# R107S1A.net
KiCad netlist of a schematic drawn in EAGLE
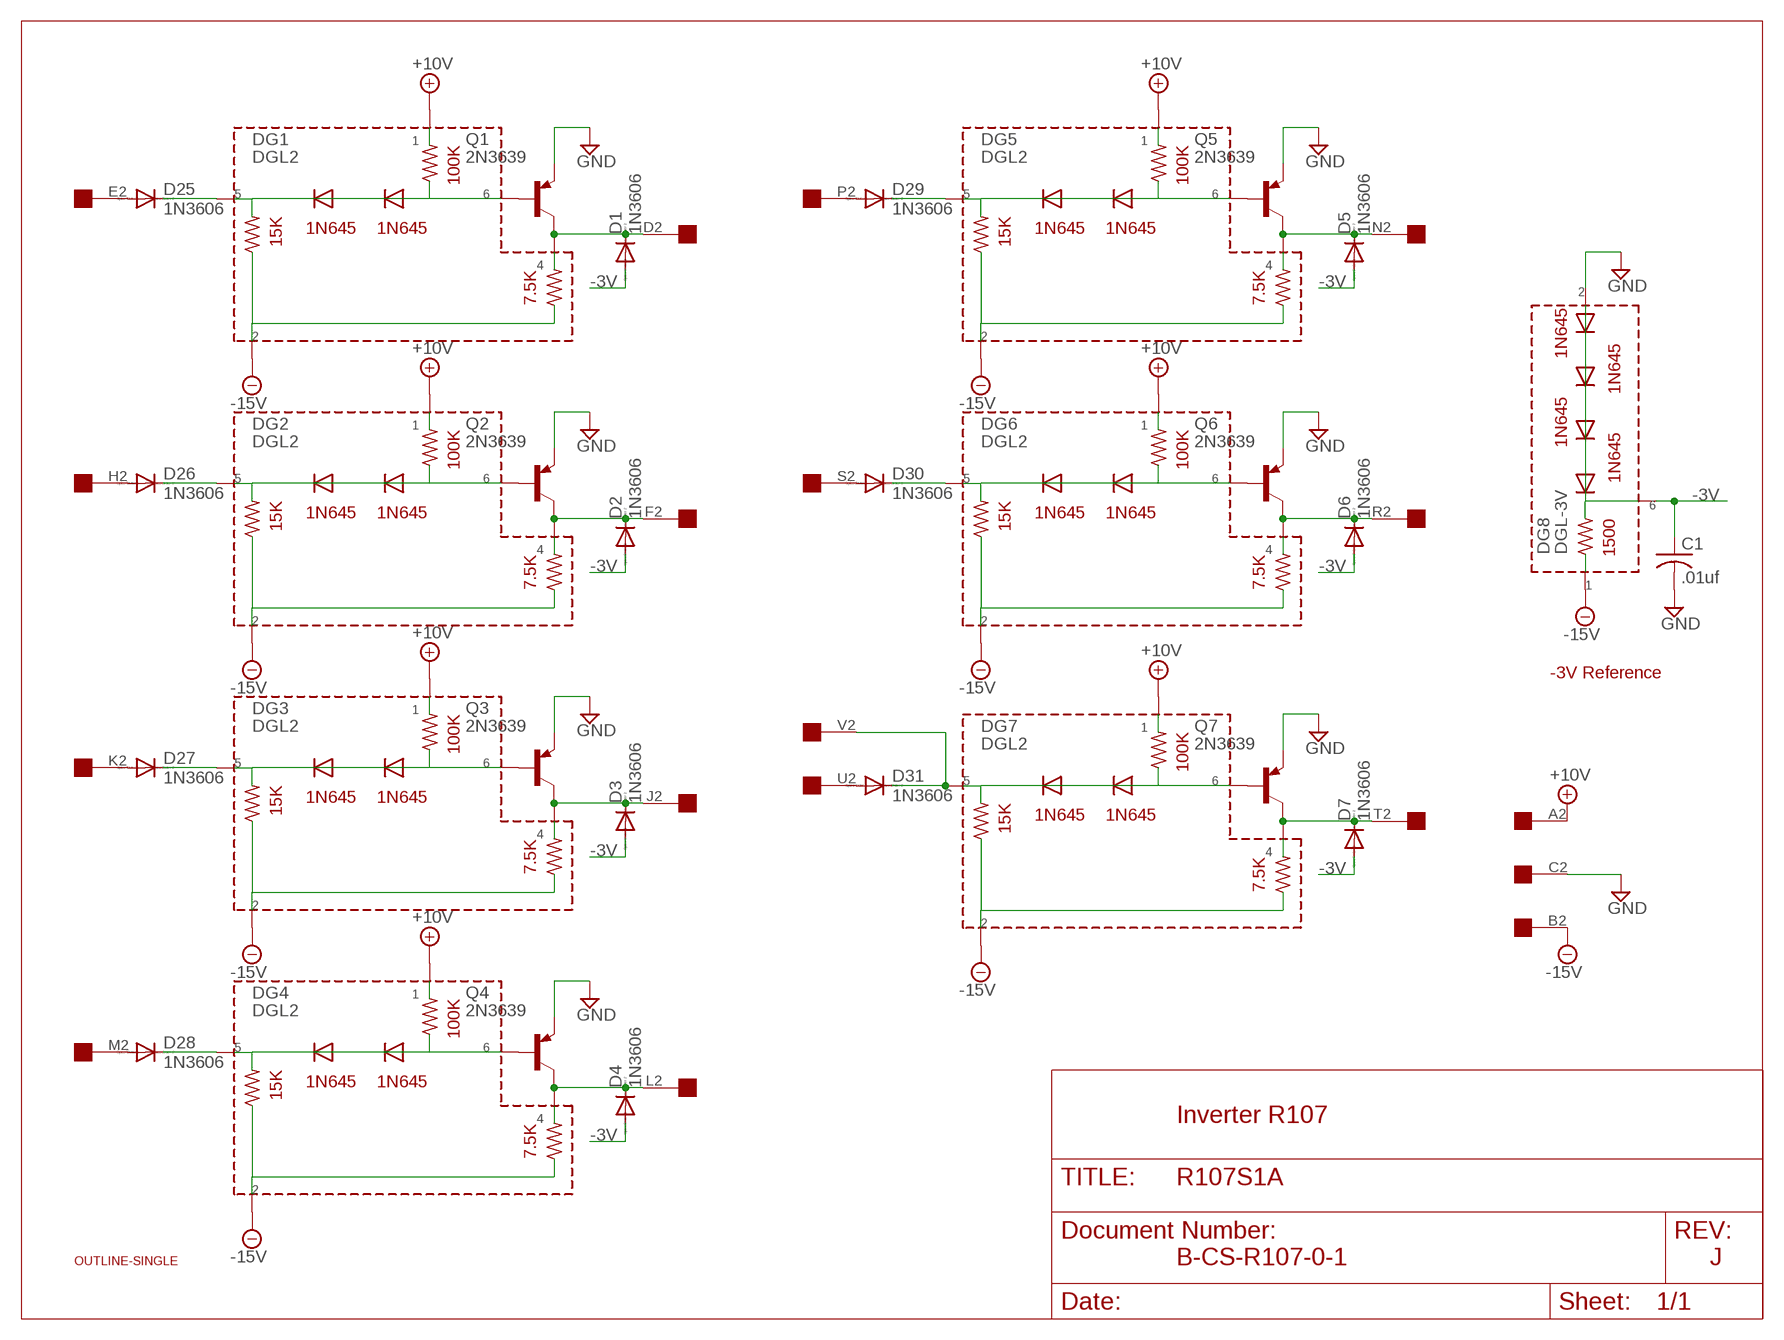
[diagram p0: schematic, sheet 1]

(export (version "E")
  (design (tool "Eeschema 10.0.6"))
  (components
    (comp (ref "C1")
      (value ".01uf")
      (footprint "eagle-import:C050-025X075")
      (libsource (lib "eagle-import") (part "C-US050-025X075"))
    )
    (comp (ref "D1")
      (value "1N3606")
      (footprint "eagle-import:DO35-10")
      (libsource (lib "eagle-import") (part "1N4148DO35-10"))
    )
    (comp (ref "D2")
      (value "1N3606")
      (footprint "eagle-import:DO35-10")
      (libsource (lib "eagle-import") (part "1N4148DO35-10"))
    )
    (comp (ref "D3")
      (value "1N3606")
      (footprint "eagle-import:DO35-10")
      (libsource (lib "eagle-import") (part "1N4148DO35-10"))
    )
    (comp (ref "D4")
      (value "1N3606")
      (footprint "eagle-import:DO35-10")
      (libsource (lib "eagle-import") (part "1N4148DO35-10"))
    )
    (comp (ref "D5")
      (value "1N3606")
      (footprint "eagle-import:DO35-10")
      (libsource (lib "eagle-import") (part "1N4148DO35-10"))
    )
    (comp (ref "D6")
      (value "1N3606")
      (footprint "eagle-import:DO35-10")
      (libsource (lib "eagle-import") (part "1N4148DO35-10"))
    )
    (comp (ref "D7")
      (value "1N3606")
      (footprint "eagle-import:DO35-10")
      (libsource (lib "eagle-import") (part "1N4148DO35-10"))
    )
    (comp (ref "D25")
      (value "1N3606")
      (footprint "eagle-import:DO35-10")
      (libsource (lib "eagle-import") (part "1N4148DO35-10"))
    )
    (comp (ref "D26")
      (value "1N3606")
      (footprint "eagle-import:DO35-10")
      (libsource (lib "eagle-import") (part "1N4148DO35-10"))
    )
    (comp (ref "D27")
      (value "1N3606")
      (footprint "eagle-import:DO35-10")
      (libsource (lib "eagle-import") (part "1N4148DO35-10"))
    )
    (comp (ref "D28")
      (value "1N3606")
      (footprint "eagle-import:DO35-10")
      (libsource (lib "eagle-import") (part "1N4148DO35-10"))
    )
    (comp (ref "D29")
      (value "1N3606")
      (footprint "eagle-import:DO35-10")
      (libsource (lib "eagle-import") (part "1N4148DO35-10"))
    )
    (comp (ref "D30")
      (value "1N3606")
      (footprint "eagle-import:DO35-10")
      (libsource (lib "eagle-import") (part "1N4148DO35-10"))
    )
    (comp (ref "D31")
      (value "1N3606")
      (footprint "eagle-import:DO35-10")
      (libsource (lib "eagle-import") (part "1N4148DO35-10"))
    )
    (comp (ref "DG1")
      (value "DGL2")
      (footprint "eagle-import:DGL2")
      (libsource (lib "eagle-import") (part "DGL2"))
    )
    (comp (ref "DG2")
      (value "DGL2")
      (footprint "eagle-import:DGL2")
      (libsource (lib "eagle-import") (part "DGL2"))
    )
    (comp (ref "DG3")
      (value "DGL2")
      (footprint "eagle-import:DGL2")
      (libsource (lib "eagle-import") (part "DGL2"))
    )
    (comp (ref "DG4")
      (value "DGL2")
      (footprint "eagle-import:DGL2")
      (libsource (lib "eagle-import") (part "DGL2"))
    )
    (comp (ref "DG5")
      (value "DGL2")
      (footprint "eagle-import:DGL2")
      (libsource (lib "eagle-import") (part "DGL2"))
    )
    (comp (ref "DG6")
      (value "DGL2")
      (footprint "eagle-import:DGL2")
      (libsource (lib "eagle-import") (part "DGL2"))
    )
    (comp (ref "DG7")
      (value "DGL2")
      (footprint "eagle-import:DGL2")
      (libsource (lib "eagle-import") (part "DGL2"))
    )
    (comp (ref "DG8")
      (value "DGL-3V")
      (footprint "eagle-import:DGL2")
      (libsource (lib "eagle-import") (part "DGL-3V"))
    )
    (comp (ref "Q1")
      (value "2N3639")
      (footprint "eagle-import:TO39")
      (libsource (lib "eagle-import") (part "2N3637"))
    )
    (comp (ref "Q2")
      (value "2N3639")
      (footprint "eagle-import:TO39")
      (libsource (lib "eagle-import") (part "2N3637"))
    )
    (comp (ref "Q3")
      (value "2N3639")
      (footprint "eagle-import:TO39")
      (libsource (lib "eagle-import") (part "2N3637"))
    )
    (comp (ref "Q4")
      (value "2N3639")
      (footprint "eagle-import:TO39")
      (libsource (lib "eagle-import") (part "2N3637"))
    )
    (comp (ref "Q5")
      (value "2N3639")
      (footprint "eagle-import:TO39")
      (libsource (lib "eagle-import") (part "2N3637"))
    )
    (comp (ref "Q6")
      (value "2N3639")
      (footprint "eagle-import:TO39")
      (libsource (lib "eagle-import") (part "2N3637"))
    )
    (comp (ref "Q7")
      (value "2N3639")
      (footprint "eagle-import:TO39")
      (libsource (lib "eagle-import") (part "2N3637"))
    )
    (comp (ref "U$1")
      (value "OUTLINE-SINGLE")
      (footprint "eagle-import:SINGLE")
      (libsource (lib "eagle-import") (part "OUTLINE-SINGLE"))
    )
    (comp (ref "U$2")
      (value "EDGE-1")
      (footprint "eagle-import:EDGE-CON1")
      (libsource (lib "eagle-import") (part "EDGE-1"))
    )
  )
  (nets
    (net (code "1") (name "+10V") (class "Default")
      (node (ref "DG1") (pin "P$1") (pinfunction "1_P$1") (pintype "passive"))
      (node (ref "DG2") (pin "P$1") (pinfunction "1_P$1") (pintype "passive"))
      (node (ref "DG3") (pin "P$1") (pinfunction "1_P$1") (pintype "passive"))
      (node (ref "DG4") (pin "P$1") (pinfunction "1_P$1") (pintype "passive"))
      (node (ref "DG5") (pin "P$1") (pinfunction "1_P$1") (pintype "passive"))
      (node (ref "DG6") (pin "P$1") (pinfunction "1_P$1") (pintype "passive"))
      (node (ref "DG7") (pin "P$1") (pinfunction "1_P$1") (pintype "passive"))
      (node (ref "U$2") (pin "A2") (pinfunction "1_A2") (pintype "bidirectional"))
    )
    (net (code "2") (name "-15V") (class "Default")
      (node (ref "DG1") (pin "P$2") (pinfunction "2_P$2") (pintype "passive"))
      (node (ref "DG2") (pin "P$2") (pinfunction "2_P$2") (pintype "passive"))
      (node (ref "DG3") (pin "P$2") (pinfunction "2_P$2") (pintype "passive"))
      (node (ref "DG4") (pin "P$2") (pinfunction "2_P$2") (pintype "passive"))
      (node (ref "DG5") (pin "P$2") (pinfunction "2_P$2") (pintype "passive"))
      (node (ref "DG6") (pin "P$2") (pinfunction "2_P$2") (pintype "passive"))
      (node (ref "DG7") (pin "P$2") (pinfunction "2_P$2") (pintype "passive"))
      (node (ref "DG8") (pin "P$1") (pinfunction "1_P$1") (pintype "passive"))
      (node (ref "U$2") (pin "B2") (pinfunction "1_B2") (pintype "bidirectional"))
    )
    (net (code "3") (name "/-3V") (class "Default")
      (node (ref "C1") (pin "1") (pinfunction "1_1") (pintype "passive"))
      (node (ref "D1") (pin "A") (pinfunction "A_A") (pintype "passive"))
      (node (ref "D2") (pin "A") (pinfunction "A_A") (pintype "passive"))
      (node (ref "D3") (pin "A") (pinfunction "A_A") (pintype "passive"))
      (node (ref "D4") (pin "A") (pinfunction "A_A") (pintype "passive"))
      (node (ref "D5") (pin "A") (pinfunction "A_A") (pintype "passive"))
      (node (ref "D6") (pin "A") (pinfunction "A_A") (pintype "passive"))
      (node (ref "D7") (pin "A") (pinfunction "A_A") (pintype "passive"))
      (node (ref "DG8") (pin "P$6") (pinfunction "6_P$6") (pintype "passive"))
    )
    (net (code "4") (name "GND") (class "Default")
      (node (ref "C1") (pin "2") (pinfunction "2_2") (pintype "passive"))
      (node (ref "DG8") (pin "P$2") (pinfunction "2_P$2") (pintype "passive"))
      (node (ref "Q1") (pin "1") (pinfunction "E_1") (pintype "passive"))
      (node (ref "Q2") (pin "1") (pinfunction "E_1") (pintype "passive"))
      (node (ref "Q3") (pin "1") (pinfunction "E_1") (pintype "passive"))
      (node (ref "Q4") (pin "1") (pinfunction "E_1") (pintype "passive"))
      (node (ref "Q5") (pin "1") (pinfunction "E_1") (pintype "passive"))
      (node (ref "Q6") (pin "1") (pinfunction "E_1") (pintype "passive"))
      (node (ref "Q7") (pin "1") (pinfunction "E_1") (pintype "passive"))
      (node (ref "U$2") (pin "C2") (pinfunction "1_C2") (pintype "bidirectional"))
    )
    (net (code "5") (name "Net-(DG1-4)") (class "Default")
      (node (ref "D1") (pin "C") (pinfunction "C_C") (pintype "passive"))
      (node (ref "DG1") (pin "P$4") (pinfunction "4_P$4") (pintype "passive"))
      (node (ref "Q1") (pin "3") (pinfunction "C_3") (pintype "passive"))
      (node (ref "U$2") (pin "D2") (pinfunction "1_D2") (pintype "bidirectional"))
    )
    (net (code "6") (name "Net-(DG1-5)") (class "Default")
      (node (ref "D25") (pin "C") (pinfunction "C_C") (pintype "passive"))
      (node (ref "DG1") (pin "P$5") (pinfunction "5_P$5") (pintype "passive"))
    )
    (net (code "7") (name "Net-(DG1-6)") (class "Default")
      (node (ref "DG1") (pin "P$6") (pinfunction "6_P$6") (pintype "passive"))
      (node (ref "Q1") (pin "2") (pinfunction "B_2") (pintype "passive"))
    )
    (net (code "8") (name "Net-(DG2-4)") (class "Default")
      (node (ref "D2") (pin "C") (pinfunction "C_C") (pintype "passive"))
      (node (ref "DG2") (pin "P$4") (pinfunction "4_P$4") (pintype "passive"))
      (node (ref "Q2") (pin "3") (pinfunction "C_3") (pintype "passive"))
      (node (ref "U$2") (pin "F2") (pinfunction "1_F2") (pintype "bidirectional"))
    )
    (net (code "9") (name "Net-(DG2-5)") (class "Default")
      (node (ref "D26") (pin "C") (pinfunction "C_C") (pintype "passive"))
      (node (ref "DG2") (pin "P$5") (pinfunction "5_P$5") (pintype "passive"))
    )
    (net (code "10") (name "Net-(DG2-6)") (class "Default")
      (node (ref "DG2") (pin "P$6") (pinfunction "6_P$6") (pintype "passive"))
      (node (ref "Q2") (pin "2") (pinfunction "B_2") (pintype "passive"))
    )
    (net (code "11") (name "Net-(DG3-4)") (class "Default")
      (node (ref "D3") (pin "C") (pinfunction "C_C") (pintype "passive"))
      (node (ref "DG3") (pin "P$4") (pinfunction "4_P$4") (pintype "passive"))
      (node (ref "Q3") (pin "3") (pinfunction "C_3") (pintype "passive"))
      (node (ref "U$2") (pin "J2") (pinfunction "1_J2") (pintype "bidirectional"))
    )
    (net (code "12") (name "Net-(DG3-5)") (class "Default")
      (node (ref "D27") (pin "C") (pinfunction "C_C") (pintype "passive"))
      (node (ref "DG3") (pin "P$5") (pinfunction "5_P$5") (pintype "passive"))
    )
    (net (code "13") (name "Net-(DG3-6)") (class "Default")
      (node (ref "DG3") (pin "P$6") (pinfunction "6_P$6") (pintype "passive"))
      (node (ref "Q3") (pin "2") (pinfunction "B_2") (pintype "passive"))
    )
    (net (code "14") (name "Net-(DG4-4)") (class "Default")
      (node (ref "D4") (pin "C") (pinfunction "C_C") (pintype "passive"))
      (node (ref "DG4") (pin "P$4") (pinfunction "4_P$4") (pintype "passive"))
      (node (ref "Q4") (pin "3") (pinfunction "C_3") (pintype "passive"))
      (node (ref "U$2") (pin "L2") (pinfunction "1_L2") (pintype "bidirectional"))
    )
    (net (code "15") (name "Net-(DG4-5)") (class "Default")
      (node (ref "D28") (pin "C") (pinfunction "C_C") (pintype "passive"))
      (node (ref "DG4") (pin "P$5") (pinfunction "5_P$5") (pintype "passive"))
    )
    (net (code "16") (name "Net-(DG4-6)") (class "Default")
      (node (ref "DG4") (pin "P$6") (pinfunction "6_P$6") (pintype "passive"))
      (node (ref "Q4") (pin "2") (pinfunction "B_2") (pintype "passive"))
    )
    (net (code "17") (name "Net-(DG5-4)") (class "Default")
      (node (ref "D5") (pin "C") (pinfunction "C_C") (pintype "passive"))
      (node (ref "DG5") (pin "P$4") (pinfunction "4_P$4") (pintype "passive"))
      (node (ref "Q5") (pin "3") (pinfunction "C_3") (pintype "passive"))
      (node (ref "U$2") (pin "N2") (pinfunction "1_N2") (pintype "bidirectional"))
    )
    (net (code "18") (name "Net-(DG5-5)") (class "Default")
      (node (ref "D29") (pin "C") (pinfunction "C_C") (pintype "passive"))
      (node (ref "DG5") (pin "P$5") (pinfunction "5_P$5") (pintype "passive"))
    )
    (net (code "19") (name "Net-(DG5-6)") (class "Default")
      (node (ref "DG5") (pin "P$6") (pinfunction "6_P$6") (pintype "passive"))
      (node (ref "Q5") (pin "2") (pinfunction "B_2") (pintype "passive"))
    )
    (net (code "20") (name "Net-(DG6-4)") (class "Default")
      (node (ref "D6") (pin "C") (pinfunction "C_C") (pintype "passive"))
      (node (ref "DG6") (pin "P$4") (pinfunction "4_P$4") (pintype "passive"))
      (node (ref "Q6") (pin "3") (pinfunction "C_3") (pintype "passive"))
      (node (ref "U$2") (pin "R2") (pinfunction "1_R2") (pintype "bidirectional"))
    )
    (net (code "21") (name "Net-(DG6-5)") (class "Default")
      (node (ref "D30") (pin "C") (pinfunction "C_C") (pintype "passive"))
      (node (ref "DG6") (pin "P$5") (pinfunction "5_P$5") (pintype "passive"))
    )
    (net (code "22") (name "Net-(DG6-6)") (class "Default")
      (node (ref "DG6") (pin "P$6") (pinfunction "6_P$6") (pintype "passive"))
      (node (ref "Q6") (pin "2") (pinfunction "B_2") (pintype "passive"))
    )
    (net (code "23") (name "Net-(DG7-4)") (class "Default")
      (node (ref "D7") (pin "C") (pinfunction "C_C") (pintype "passive"))
      (node (ref "DG7") (pin "P$4") (pinfunction "4_P$4") (pintype "passive"))
      (node (ref "Q7") (pin "3") (pinfunction "C_3") (pintype "passive"))
      (node (ref "U$2") (pin "T2") (pinfunction "1_T2") (pintype "bidirectional"))
    )
    (net (code "24") (name "Net-(DG7-5)") (class "Default")
      (node (ref "D31") (pin "C") (pinfunction "C_C") (pintype "passive"))
      (node (ref "DG7") (pin "P$5") (pinfunction "5_P$5") (pintype "passive"))
      (node (ref "U$2") (pin "V2") (pinfunction "1_V2") (pintype "bidirectional"))
    )
    (net (code "25") (name "Net-(DG7-6)") (class "Default")
      (node (ref "DG7") (pin "P$6") (pinfunction "6_P$6") (pintype "passive"))
      (node (ref "Q7") (pin "2") (pinfunction "B_2") (pintype "passive"))
    )
    (net (code "26") (name "Net-(U$2E-1)") (class "Default")
      (node (ref "D25") (pin "A") (pinfunction "A_A") (pintype "passive"))
      (node (ref "U$2") (pin "E2") (pinfunction "1_E2") (pintype "bidirectional"))
    )
    (net (code "27") (name "Net-(U$2G-1)") (class "Default")
      (node (ref "D26") (pin "A") (pinfunction "A_A") (pintype "passive"))
      (node (ref "U$2") (pin "H2") (pinfunction "1_H2") (pintype "bidirectional"))
    )
    (net (code "28") (name "Net-(U$2I-1)") (class "Default")
      (node (ref "D27") (pin "A") (pinfunction "A_A") (pintype "passive"))
      (node (ref "U$2") (pin "K2") (pinfunction "1_K2") (pintype "bidirectional"))
    )
    (net (code "29") (name "Net-(U$2K-1)") (class "Default")
      (node (ref "D28") (pin "A") (pinfunction "A_A") (pintype "passive"))
      (node (ref "U$2") (pin "M2") (pinfunction "1_M2") (pintype "bidirectional"))
    )
    (net (code "30") (name "Net-(U$2M-1)") (class "Default")
      (node (ref "D29") (pin "A") (pinfunction "A_A") (pintype "passive"))
      (node (ref "U$2") (pin "P2") (pinfunction "1_P2") (pintype "bidirectional"))
    )
    (net (code "31") (name "Net-(U$2O-1)") (class "Default")
      (node (ref "D30") (pin "A") (pinfunction "A_A") (pintype "passive"))
      (node (ref "U$2") (pin "S2") (pinfunction "1_S2") (pintype "bidirectional"))
    )
    (net (code "32") (name "Net-(U$2Q-1)") (class "Default")
      (node (ref "D31") (pin "A") (pinfunction "A_A") (pintype "passive"))
      (node (ref "U$2") (pin "U2") (pinfunction "1_U2") (pintype "bidirectional"))
    )
  )
)
